# ZYNQ400-POWER.net
KiCad netlist of a schematic drawn in Altium Designer
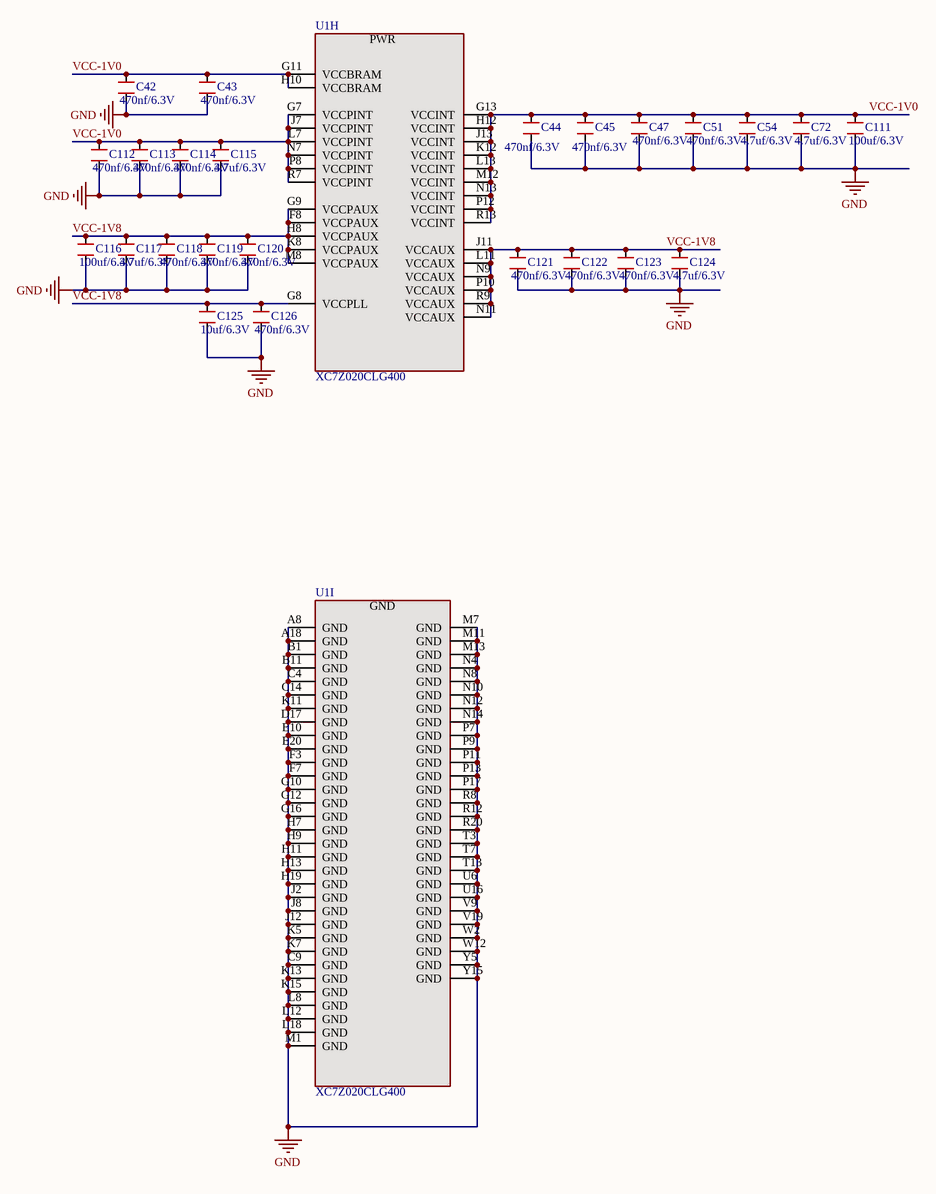
[diagram p0: ZYNQ400-POWER.SchDoc]

(export (version "E")
  (design (tool "Eeschema 10.0.6"))
  (components
    (comp (ref "C42")
      (value "470nf/6.3V")
      (footprint "0402")
      (description "Generic Capacitor")
      (libsource (lib "Digilent") (part "CAPACITOR"))
    )
    (comp (ref "C43")
      (value "470nf/6.3V")
      (footprint "0402")
      (description "Generic Capacitor")
      (libsource (lib "Digilent") (part "CAPACITOR"))
    )
    (comp (ref "C44")
      (value "470nf/6.3V")
      (footprint "0402")
      (description "Generic Capacitor")
      (libsource (lib "Digilent") (part "CAPACITOR"))
    )
    (comp (ref "C45")
      (value "470nf/6.3V")
      (footprint "0402")
      (description "Generic Capacitor")
      (libsource (lib "Digilent") (part "CAPACITOR"))
    )
    (comp (ref "C47")
      (value "470nf/6.3V")
      (footprint "0402")
      (description "Generic Capacitor")
      (libsource (lib "Digilent") (part "CAPACITOR"))
    )
    (comp (ref "C51")
      (value "470nf/6.3V")
      (footprint "0402")
      (description "Generic Capacitor")
      (libsource (lib "Digilent") (part "CAPACITOR"))
    )
    (comp (ref "C54")
      (value "4.7uf/6.3V")
      (footprint "0402")
      (description "Generic Capacitor")
      (libsource (lib "Digilent") (part "CAPACITOR"))
    )
    (comp (ref "C72")
      (value "4.7uf/6.3V")
      (footprint "0402")
      (description "Generic Capacitor")
      (libsource (lib "Digilent") (part "CAPACITOR"))
    )
    (comp (ref "C111")
      (value "100uf/6.3V")
      (footprint "0805")
      (description "Generic Capacitor")
      (libsource (lib "Digilent") (part "CAPACITOR"))
    )
    (comp (ref "C112")
      (value "470nf/6.3V")
      (footprint "0402")
      (description "Generic Capacitor")
      (libsource (lib "Digilent") (part "CAPACITOR"))
    )
    (comp (ref "C113")
      (value "470nf/6.3V")
      (footprint "0402")
      (description "Generic Capacitor")
      (libsource (lib "Digilent") (part "CAPACITOR"))
    )
    (comp (ref "C114")
      (value "470nf/6.3V")
      (footprint "0402")
      (description "Generic Capacitor")
      (libsource (lib "Digilent") (part "CAPACITOR"))
    )
    (comp (ref "C115")
      (value "4.7uf/6.3V")
      (footprint "0402")
      (description "Generic Capacitor")
      (libsource (lib "Digilent") (part "CAPACITOR"))
    )
    (comp (ref "C116")
      (value "100uf/6.3V")
      (footprint "0805")
      (description "Generic Capacitor")
      (libsource (lib "Digilent") (part "CAPACITOR"))
    )
    (comp (ref "C117")
      (value "4.7uf/6.3V")
      (footprint "0402")
      (description "Generic Capacitor")
      (libsource (lib "Digilent") (part "CAPACITOR"))
    )
    (comp (ref "C118")
      (value "470nf/6.3V")
      (footprint "0402")
      (description "Generic Capacitor")
      (libsource (lib "Digilent") (part "CAPACITOR"))
    )
    (comp (ref "C119")
      (value "470nf/6.3V")
      (footprint "0402")
      (description "Generic Capacitor")
      (libsource (lib "Digilent") (part "CAPACITOR"))
    )
    (comp (ref "C120")
      (value "470nf/6.3V")
      (footprint "0402")
      (description "Generic Capacitor")
      (libsource (lib "Digilent") (part "CAPACITOR"))
    )
    (comp (ref "C121")
      (value "470nf/6.3V")
      (footprint "0402")
      (description "Generic Capacitor")
      (libsource (lib "Digilent") (part "CAPACITOR"))
    )
    (comp (ref "C122")
      (value "470nf/6.3V")
      (footprint "0402")
      (description "Generic Capacitor")
      (libsource (lib "Digilent") (part "CAPACITOR"))
    )
    (comp (ref "C123")
      (value "470nf/6.3V")
      (footprint "0402")
      (description "Generic Capacitor")
      (libsource (lib "Digilent") (part "CAPACITOR"))
    )
    (comp (ref "C124")
      (value "4.7uf/6.3V")
      (footprint "0402")
      (description "Generic Capacitor")
      (libsource (lib "Digilent") (part "CAPACITOR"))
    )
    (comp (ref "C125")
      (value "10uf/6.3V")
      (footprint "0603")
      (description "Generic Capacitor")
      (libsource (lib "Digilent") (part "CAPACITOR"))
    )
    (comp (ref "C126")
      (value "470nf/6.3V")
      (footprint "0402")
      (description "Generic Capacitor")
      (libsource (lib "Digilent") (part "CAPACITOR"))
    )
    (comp (ref "U1")
      (value "XC7Z020CLG400")
      (footprint "CLG400")
      (description "Zynq 7000 FPGA 20 Die, in a CSG 484 Package")
      (fields (field (name "MANUFACTURER") "Xilinx"))
      (libsource (lib "gjws") (part "XC7Z020-CLG400"))
    )
  )
  (nets
    (net (code "1") (name "/VCC-1V0") (class "Default")
      (node (ref "C111") (pin "1") (pinfunction "1_1") (pintype "passive"))
      (node (ref "C112") (pin "1") (pinfunction "1_1") (pintype "passive"))
      (node (ref "C113") (pin "1") (pinfunction "1_1") (pintype "passive"))
      (node (ref "C114") (pin "1") (pinfunction "1_1") (pintype "passive"))
      (node (ref "C115") (pin "1") (pinfunction "1_1") (pintype "passive"))
      (node (ref "C42") (pin "1") (pinfunction "1_1") (pintype "passive"))
      (node (ref "C43") (pin "1") (pinfunction "1_1") (pintype "passive"))
      (node (ref "C44") (pin "1") (pinfunction "1_1") (pintype "passive"))
      (node (ref "C45") (pin "1") (pinfunction "1_1") (pintype "passive"))
      (node (ref "C47") (pin "1") (pinfunction "1_1") (pintype "passive"))
      (node (ref "C51") (pin "1") (pinfunction "1_1") (pintype "passive"))
      (node (ref "C54") (pin "1") (pinfunction "1_1") (pintype "passive"))
      (node (ref "C72") (pin "1") (pinfunction "1_1") (pintype "passive"))
      (node (ref "U1") (pin "G11") (pinfunction "VCCBRAM_G11") (pintype "power_in"))
      (node (ref "U1") (pin "G13") (pinfunction "VCCINT_G13") (pintype "power_in"))
      (node (ref "U1") (pin "G7") (pinfunction "VCCPINT_G7") (pintype "power_in"))
      (node (ref "U1") (pin "H10") (pinfunction "VCCBRAM_H10") (pintype "power_in"))
      (node (ref "U1") (pin "H12") (pinfunction "VCCINT_H12") (pintype "power_in"))
      (node (ref "U1") (pin "J13") (pinfunction "VCCINT_J13") (pintype "power_in"))
      (node (ref "U1") (pin "J7") (pinfunction "VCCPINT_J7") (pintype "power_in"))
      (node (ref "U1") (pin "K12") (pinfunction "VCCINT_K12") (pintype "power_in"))
      (node (ref "U1") (pin "L13") (pinfunction "VCCINT_L13") (pintype "power_in"))
      (node (ref "U1") (pin "L7") (pinfunction "VCCPINT_L7") (pintype "power_in"))
      (node (ref "U1") (pin "M12") (pinfunction "VCCINT_M12") (pintype "power_in"))
      (node (ref "U1") (pin "N13") (pinfunction "VCCINT_N13") (pintype "power_in"))
      (node (ref "U1") (pin "N7") (pinfunction "VCCPINT_N7") (pintype "power_in"))
      (node (ref "U1") (pin "P12") (pinfunction "VCCINT_P12") (pintype "power_in"))
      (node (ref "U1") (pin "P8") (pinfunction "VCCPINT_P8") (pintype "power_in"))
      (node (ref "U1") (pin "R13") (pinfunction "VCCINT_R13") (pintype "power_in"))
      (node (ref "U1") (pin "R7") (pinfunction "VCCPINT_R7") (pintype "power_in"))
    )
    (net (code "2") (name "/VCC-1V8") (class "Default")
      (node (ref "C116") (pin "1") (pinfunction "1_1") (pintype "passive"))
      (node (ref "C117") (pin "1") (pinfunction "1_1") (pintype "passive"))
      (node (ref "C118") (pin "1") (pinfunction "1_1") (pintype "passive"))
      (node (ref "C119") (pin "1") (pinfunction "1_1") (pintype "passive"))
      (node (ref "C120") (pin "1") (pinfunction "1_1") (pintype "passive"))
      (node (ref "C121") (pin "1") (pinfunction "1_1") (pintype "passive"))
      (node (ref "C122") (pin "1") (pinfunction "1_1") (pintype "passive"))
      (node (ref "C123") (pin "1") (pinfunction "1_1") (pintype "passive"))
      (node (ref "C124") (pin "1") (pinfunction "1_1") (pintype "passive"))
      (node (ref "C125") (pin "1") (pinfunction "1_1") (pintype "passive"))
      (node (ref "C126") (pin "1") (pinfunction "1_1") (pintype "passive"))
      (node (ref "U1") (pin "F8") (pinfunction "VCCPAUX_F8") (pintype "power_in"))
      (node (ref "U1") (pin "G8") (pinfunction "VCCPLL_G8") (pintype "power_in"))
      (node (ref "U1") (pin "G9") (pinfunction "VCCPAUX_G9") (pintype "power_in"))
      (node (ref "U1") (pin "H8") (pinfunction "VCCPAUX_H8") (pintype "power_in"))
      (node (ref "U1") (pin "J11") (pinfunction "VCCAUX_J11") (pintype "power_in"))
      (node (ref "U1") (pin "K8") (pinfunction "VCCPAUX_K8") (pintype "power_in"))
      (node (ref "U1") (pin "L11") (pinfunction "VCCAUX_L11") (pintype "power_in"))
      (node (ref "U1") (pin "M8") (pinfunction "VCCPAUX_M8") (pintype "power_in"))
      (node (ref "U1") (pin "N11") (pinfunction "VCCAUX_N11") (pintype "power_in"))
      (node (ref "U1") (pin "N9") (pinfunction "VCCAUX_N9") (pintype "power_in"))
      (node (ref "U1") (pin "P10") (pinfunction "VCCAUX_P10") (pintype "power_in"))
      (node (ref "U1") (pin "R9") (pinfunction "VCCAUX_R9") (pintype "power_in"))
    )
    (net (code "3") (name "GND") (class "Default")
      (node (ref "C111") (pin "2") (pinfunction "2_2") (pintype "passive"))
      (node (ref "C112") (pin "2") (pinfunction "2_2") (pintype "passive"))
      (node (ref "C113") (pin "2") (pinfunction "2_2") (pintype "passive"))
      (node (ref "C114") (pin "2") (pinfunction "2_2") (pintype "passive"))
      (node (ref "C115") (pin "2") (pinfunction "2_2") (pintype "passive"))
      (node (ref "C116") (pin "2") (pinfunction "2_2") (pintype "passive"))
      (node (ref "C117") (pin "2") (pinfunction "2_2") (pintype "passive"))
      (node (ref "C118") (pin "2") (pinfunction "2_2") (pintype "passive"))
      (node (ref "C119") (pin "2") (pinfunction "2_2") (pintype "passive"))
      (node (ref "C120") (pin "2") (pinfunction "2_2") (pintype "passive"))
      (node (ref "C121") (pin "2") (pinfunction "2_2") (pintype "passive"))
      (node (ref "C122") (pin "2") (pinfunction "2_2") (pintype "passive"))
      (node (ref "C123") (pin "2") (pinfunction "2_2") (pintype "passive"))
      (node (ref "C124") (pin "2") (pinfunction "2_2") (pintype "passive"))
      (node (ref "C125") (pin "2") (pinfunction "2_2") (pintype "passive"))
      (node (ref "C126") (pin "2") (pinfunction "2_2") (pintype "passive"))
      (node (ref "C42") (pin "2") (pinfunction "2_2") (pintype "passive"))
      (node (ref "C43") (pin "2") (pinfunction "2_2") (pintype "passive"))
      (node (ref "C44") (pin "2") (pinfunction "2_2") (pintype "passive"))
      (node (ref "C45") (pin "2") (pinfunction "2_2") (pintype "passive"))
      (node (ref "C47") (pin "2") (pinfunction "2_2") (pintype "passive"))
      (node (ref "C51") (pin "2") (pinfunction "2_2") (pintype "passive"))
      (node (ref "C54") (pin "2") (pinfunction "2_2") (pintype "passive"))
      (node (ref "C72") (pin "2") (pinfunction "2_2") (pintype "passive"))
      (node (ref "U1") (pin "A18") (pinfunction "GND_A18") (pintype "power_in"))
      (node (ref "U1") (pin "A8") (pinfunction "GND_A8") (pintype "power_in"))
      (node (ref "U1") (pin "B1") (pinfunction "GND_B1") (pintype "power_in"))
      (node (ref "U1") (pin "B11") (pinfunction "GND_B11") (pintype "power_in"))
      (node (ref "U1") (pin "C14") (pinfunction "GND_C14") (pintype "power_in"))
      (node (ref "U1") (pin "C4") (pinfunction "GND_C4") (pintype "power_in"))
      (node (ref "U1") (pin "C9") (pinfunction "GND_C9") (pintype "power_in"))
      (node (ref "U1") (pin "D17") (pinfunction "GND_D17") (pintype "power_in"))
      (node (ref "U1") (pin "E10") (pinfunction "GND_E10") (pintype "power_in"))
      (node (ref "U1") (pin "E20") (pinfunction "GND_E20") (pintype "power_in"))
      (node (ref "U1") (pin "F3") (pinfunction "GND_F3") (pintype "power_in"))
      (node (ref "U1") (pin "F7") (pinfunction "GND_F7") (pintype "power_in"))
      (node (ref "U1") (pin "G10") (pinfunction "GND_G10") (pintype "power_in"))
      (node (ref "U1") (pin "G12") (pinfunction "GND_G12") (pintype "power_in"))
      (node (ref "U1") (pin "G16") (pinfunction "GND_G16") (pintype "power_in"))
      (node (ref "U1") (pin "H11") (pinfunction "GND_H11") (pintype "power_in"))
      (node (ref "U1") (pin "H13") (pinfunction "GND_H13") (pintype "power_in"))
      (node (ref "U1") (pin "H19") (pinfunction "GND_H19") (pintype "power_in"))
      (node (ref "U1") (pin "H7") (pinfunction "GND_H7") (pintype "power_in"))
      (node (ref "U1") (pin "H9") (pinfunction "GND_H9") (pintype "power_in"))
      (node (ref "U1") (pin "J12") (pinfunction "GND_J12") (pintype "power_in"))
      (node (ref "U1") (pin "J2") (pinfunction "GND_J2") (pintype "power_in"))
      (node (ref "U1") (pin "J8") (pinfunction "GND_J8") (pintype "power_in"))
      (node (ref "U1") (pin "K11") (pinfunction "GND_K11") (pintype "power_in"))
      (node (ref "U1") (pin "K13") (pinfunction "GND_K13") (pintype "power_in"))
      (node (ref "U1") (pin "K15") (pinfunction "GND_K15") (pintype "power_in"))
      (node (ref "U1") (pin "K5") (pinfunction "GND_K5") (pintype "power_in"))
      (node (ref "U1") (pin "K7") (pinfunction "GND_K7") (pintype "power_in"))
      (node (ref "U1") (pin "L12") (pinfunction "GND_L12") (pintype "power_in"))
      (node (ref "U1") (pin "L18") (pinfunction "GND_L18") (pintype "power_in"))
      (node (ref "U1") (pin "L8") (pinfunction "GND_L8") (pintype "power_in"))
      (node (ref "U1") (pin "M1") (pinfunction "GND_M1") (pintype "power_in"))
      (node (ref "U1") (pin "M11") (pinfunction "GND_M11") (pintype "power_in"))
      (node (ref "U1") (pin "M13") (pinfunction "GND_M13") (pintype "power_in"))
      (node (ref "U1") (pin "M7") (pinfunction "GND_M7") (pintype "power_in"))
      (node (ref "U1") (pin "N10") (pinfunction "GND_N10") (pintype "power_in"))
      (node (ref "U1") (pin "N12") (pinfunction "GND_N12") (pintype "power_in"))
      (node (ref "U1") (pin "N14") (pinfunction "GND_N14") (pintype "power_in"))
      (node (ref "U1") (pin "N4") (pinfunction "GND_N4") (pintype "power_in"))
      (node (ref "U1") (pin "N8") (pinfunction "GND_N8") (pintype "power_in"))
      (node (ref "U1") (pin "P11") (pinfunction "GND_P11") (pintype "power_in"))
      (node (ref "U1") (pin "P13") (pinfunction "GND_P13") (pintype "power_in"))
      (node (ref "U1") (pin "P17") (pinfunction "GND_P17") (pintype "power_in"))
      (node (ref "U1") (pin "P7") (pinfunction "GND_P7") (pintype "power_in"))
      (node (ref "U1") (pin "P9") (pinfunction "GND_P9") (pintype "power_in"))
      (node (ref "U1") (pin "R12") (pinfunction "GND_R12") (pintype "power_in"))
      (node (ref "U1") (pin "R20") (pinfunction "GND_R20") (pintype "power_in"))
      (node (ref "U1") (pin "R8") (pinfunction "GND_R8") (pintype "power_in"))
      (node (ref "U1") (pin "T13") (pinfunction "GND_T13") (pintype "power_in"))
      (node (ref "U1") (pin "T3") (pinfunction "GND_T3") (pintype "power_in"))
      (node (ref "U1") (pin "T7") (pinfunction "GND_T7") (pintype "power_in"))
      (node (ref "U1") (pin "U16") (pinfunction "GND_U16") (pintype "power_in"))
      (node (ref "U1") (pin "U6") (pinfunction "GND_U6") (pintype "power_in"))
      (node (ref "U1") (pin "V19") (pinfunction "GND_V19") (pintype "power_in"))
      (node (ref "U1") (pin "V9") (pinfunction "GND_V9") (pintype "power_in"))
      (node (ref "U1") (pin "W12") (pinfunction "GND_W12") (pintype "power_in"))
      (node (ref "U1") (pin "W2") (pinfunction "GND_W2") (pintype "power_in"))
      (node (ref "U1") (pin "Y15") (pinfunction "GND_Y15") (pintype "power_in"))
      (node (ref "U1") (pin "Y5") (pinfunction "GND_Y5") (pintype "power_in"))
    )
  )
)
